# MCU_Schematic_Winterbreak.net
KiCad netlist of a schematic drawn in Altium Designer
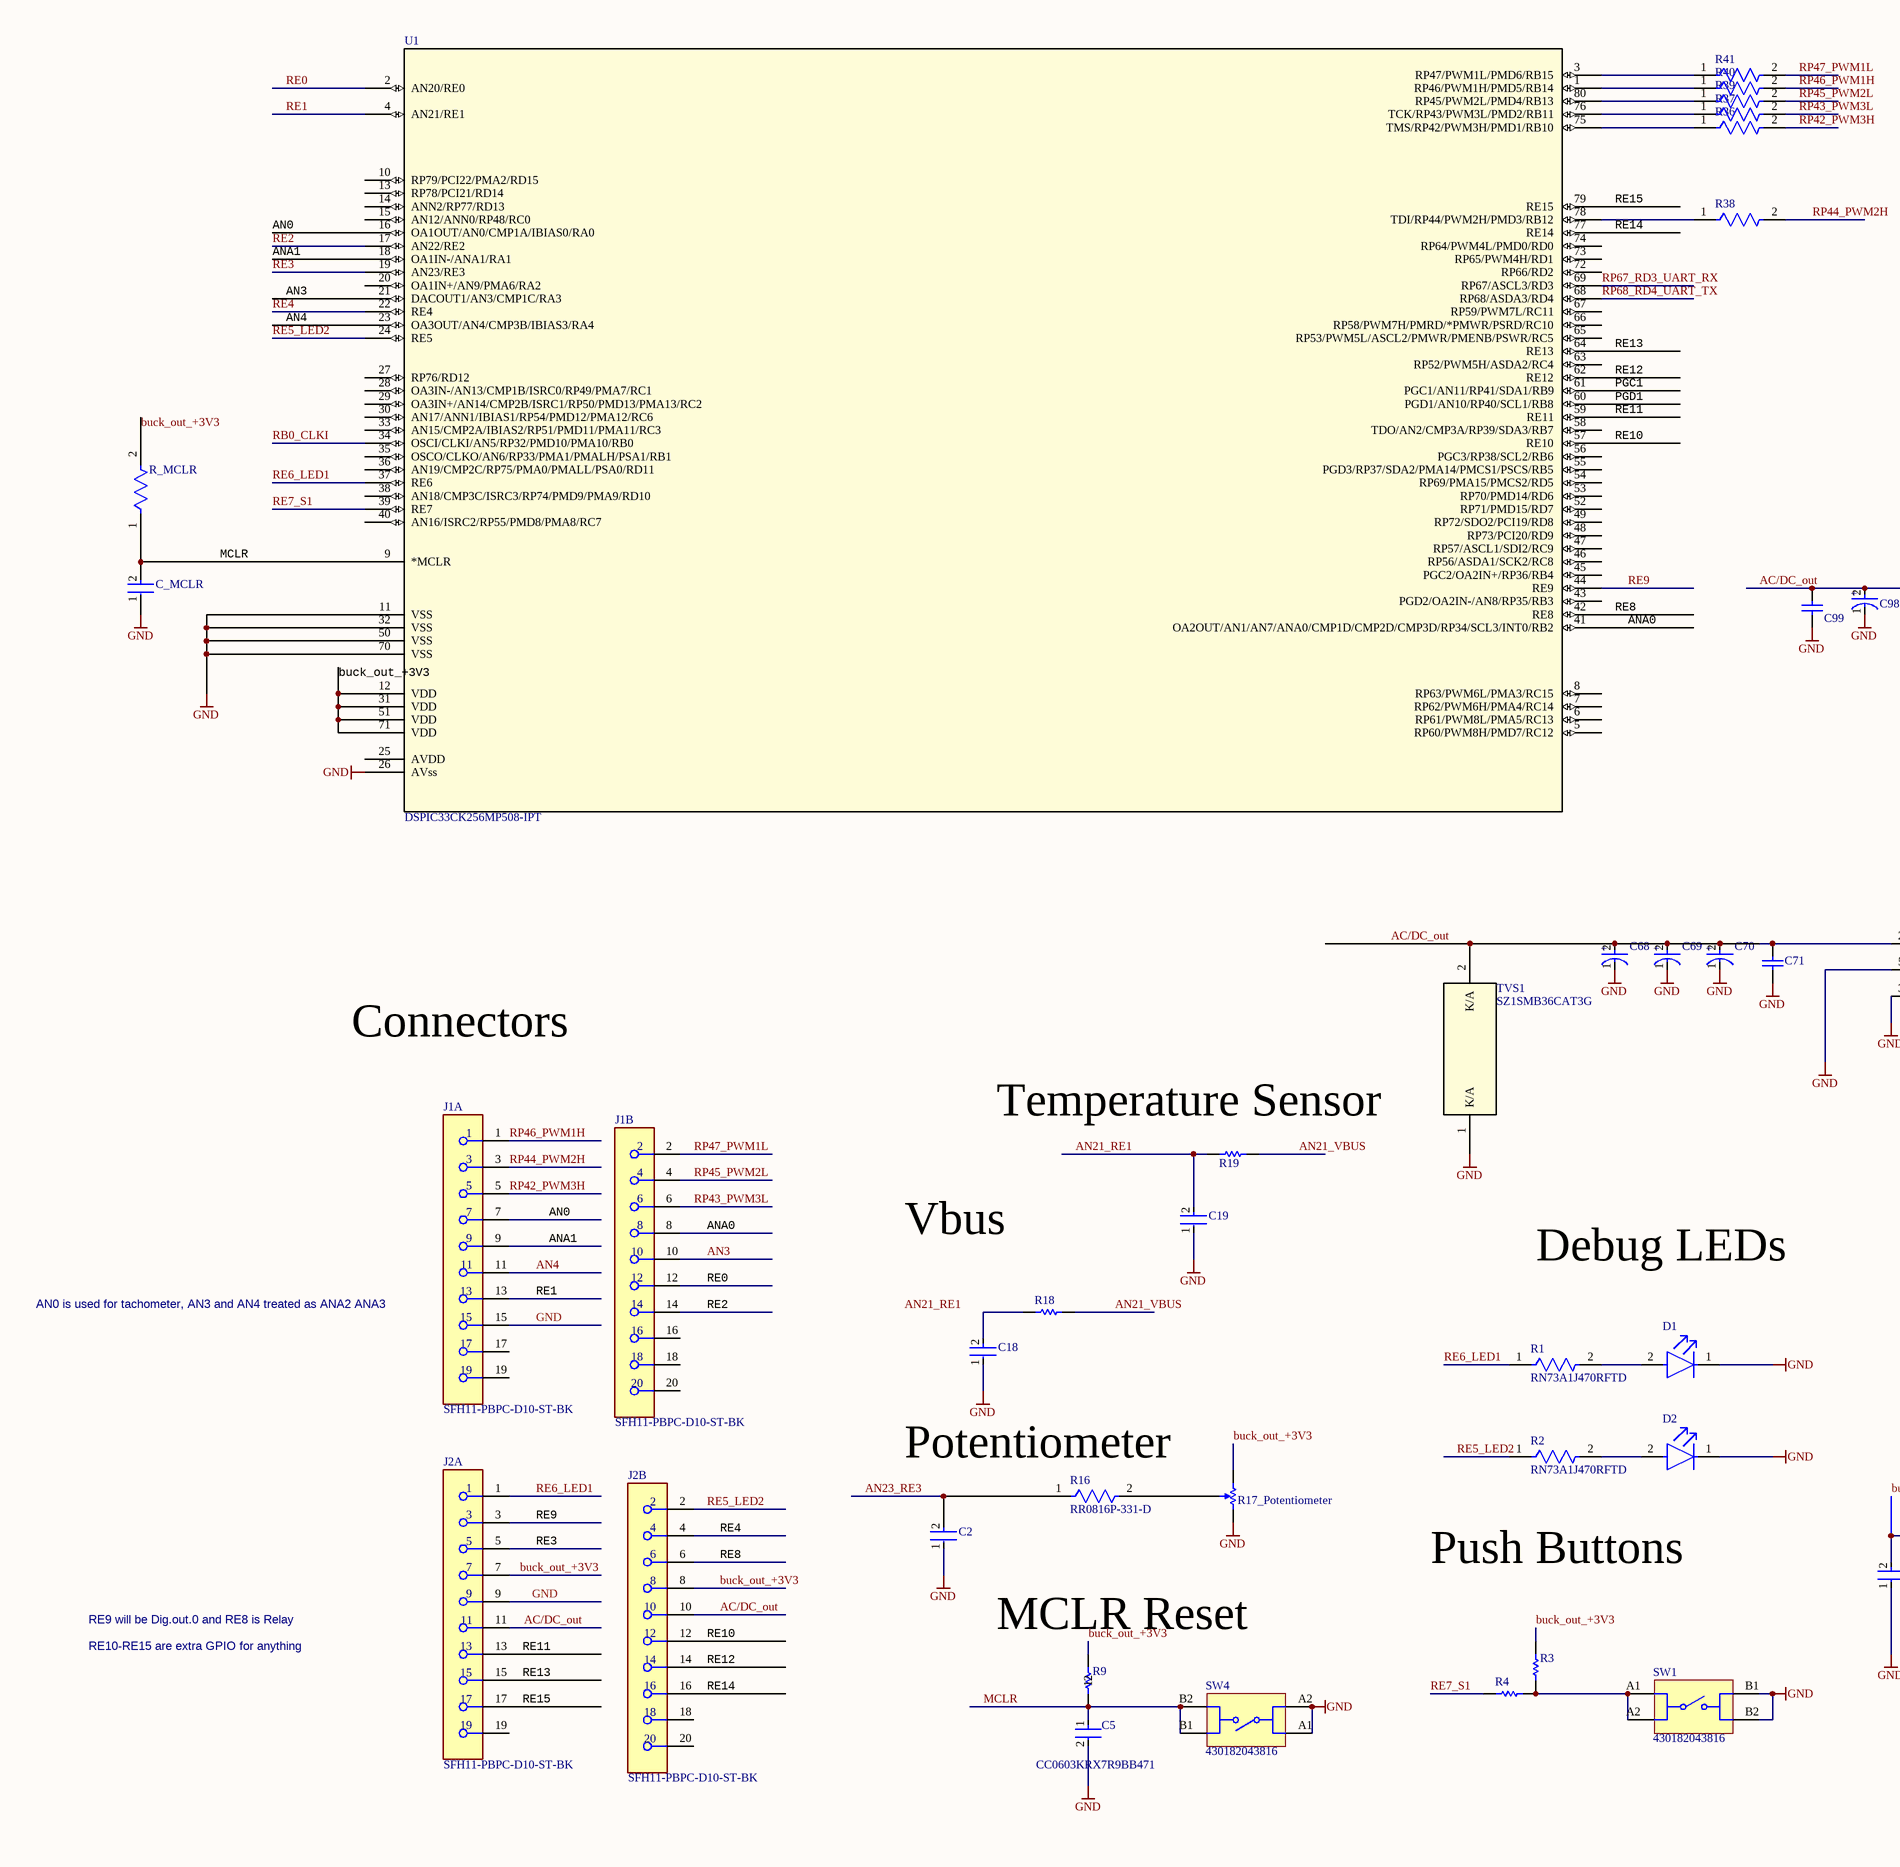
[diagram p0: MCU_Schematic_Winterbreak.SchDoc, left]
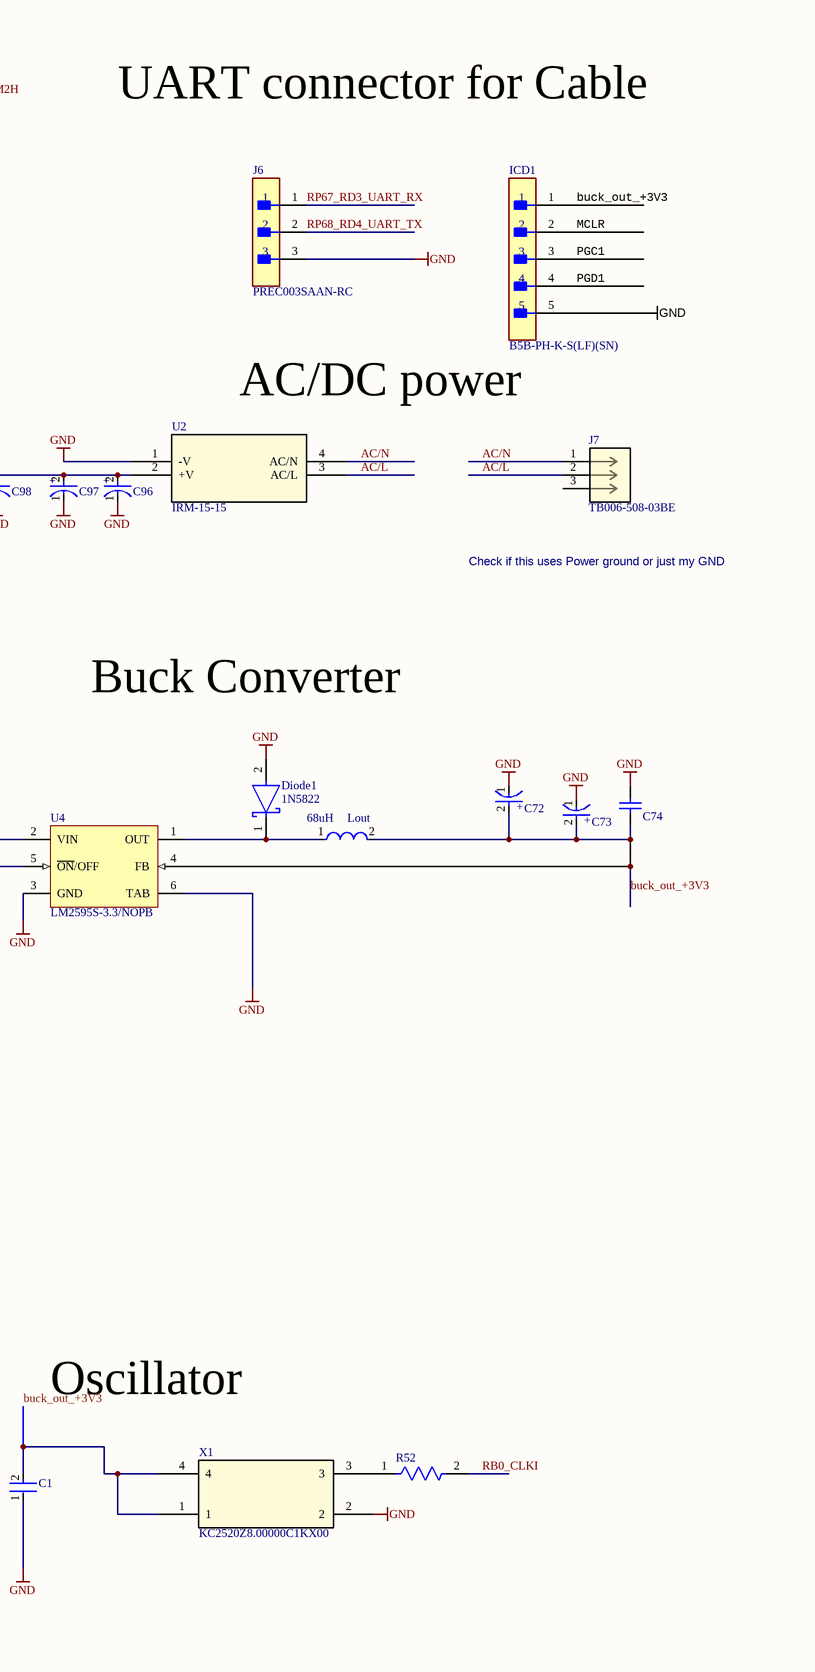
[diagram p1: MCU_Schematic_Winterbreak.SchDoc, right]

(export (version "E")
  (design (tool "Eeschema 10.0.6"))
  (components
    (comp (ref "C1")
      (value "GRM155R71C104KA88D")
      (footprint "FP-GRM15-MFG")
      (description "CAP CER 0.1UF 16V X7R 0402")
      (fields
        (field (name "TOLERANCE") "10%")
        (field (name "OCTOPART") "https://octopart.com/grm155r71c104ka88d-murata-196880")
      )
      (libsource (lib "Altium Content Vault") (part "236180d848d6139a670b325ea6854c9"))
    )
    (comp (ref "C2")
      (value "GRM155R71C104KA88D")
      (footprint "FP-GRM15-MFG")
      (description "CAP CER 0.1UF 16V X7R 0402")
      (fields
        (field (name "TOLERANCE") "10%")
        (field (name "OCTOPART") "https://octopart.com/grm155r71c104ka88d-murata-196880")
      )
      (libsource (lib "Altium Content Vault") (part "236180d848d6139a670b325ea6854c9"))
    )
    (comp (ref "C5")
      (value "CC0603KRX7R9BB471")
      (footprint "FP-CC0603-DA-MFG")
      (description "CAP CER 470PF 50V X7R 0603")
      (fields
        (field (name "VOLTAGE") "50 V")
        (field (name "OCTOPART") "https://octopart.com/cc0603krx7r9bb471-yageo-192931")
      )
      (libsource (lib "Altium Content Vault") (part "11868f565c42a9108669ba33697ecf6"))
    )
    (comp (ref "C18")
      (value "GRM155R71C104KA88D")
      (footprint "FP-GRM15-MFG")
      (description "CAP CER 0.1UF 16V X7R 0402")
      (fields
        (field (name "TOLERANCE") "10%")
        (field (name "OCTOPART") "https://octopart.com/grm155r71c104ka88d-murata-196880")
      )
      (libsource (lib "Altium Content Vault") (part "236180d848d6139a670b325ea6854c9"))
    )
    (comp (ref "C19")
      (value "GRM155R71C104KA88D")
      (footprint "FP-GRM15-MFG")
      (description "CAP CER 0.1UF 16V X7R 0402")
      (fields
        (field (name "TOLERANCE") "10%")
        (field (name "OCTOPART") "https://octopart.com/grm155r71c104ka88d-murata-196880")
      )
      (libsource (lib "Altium Content Vault") (part "236180d848d6139a670b325ea6854c9"))
    )
    (comp (ref "C68")
      (value "EEHAZS1H221B")
      (footprint "FP-EEHA-G16-MFG")
      (description "Conductive Polymer Hybrid Aluminum Electrolytic Capacitors 220uF ±20% 50V RADIAL TH 10x15.7mm")
      (libsource (lib "Altium Content Vault") (part "203bc49f2ac43e59fd269a8c329ed05"))
    )
    (comp (ref "C69")
      (value "EEHAZS1H221B")
      (footprint "FP-EEHA-G16-MFG")
      (description "Conductive Polymer Hybrid Aluminum Electrolytic Capacitors 220uF ±20% 50V RADIAL TH 10x15.7mm")
      (libsource (lib "Altium Content Vault") (part "203bc49f2ac43e59fd269a8c329ed05"))
    )
    (comp (ref "C70")
      (value "TAJE476K035RNJ")
      (footprint "FP-TAJE-MFG")
      (description "47uF 35V  ±10% 900mΩ 2917  SMD Tantalum Capacitor")
      (fields (field (name "VOLTAGE") "35V") (field (name "TOLERANCE") "10%"))
      (libsource (lib "Altium Content Vault") (part "203bc49f2ac43e59fd269a8c329ed05"))
    )
    (comp (ref "C71")
      (value "08055C104KAZ2A")
      (footprint "CAPC2013X94X50NL20T25")
      (fields (field (name "MANUFACTURER") "AVX Interconnect / Elco"))
      (libsource (lib "Altium Content Vault") (part "CAP"))
    )
    (comp (ref "C72")
      (value "EEHAZS1H221B")
      (footprint "FP-EEHA-G16-MFG")
      (description "Conductive Polymer Hybrid Aluminum Electrolytic Capacitors 220uF ±20% 50V RADIAL TH 10x15.7mm")
      (libsource (lib "Altium Content Vault") (part "203bc49f2ac43e59fd269a8c329ed05"))
    )
    (comp (ref "C73")
      (value "TAJE476K035RNJ")
      (footprint "FP-TAJE-MFG")
      (description "47uF 35V  ±10% 900mΩ 2917  SMD Tantalum Capacitor")
      (fields (field (name "VOLTAGE") "35V") (field (name "TOLERANCE") "10%"))
      (libsource (lib "Altium Content Vault") (part "203bc49f2ac43e59fd269a8c329ed05"))
    )
    (comp (ref "C74")
      (value "08055C104KAZ2A")
      (footprint "CAPC2013X94X50NL20T25")
      (fields (field (name "MANUFACTURER") "AVX Interconnect / Elco"))
      (libsource (lib "Altium Content Vault") (part "CAP"))
    )
    (comp (ref "C96")
      (value "EEHAZS1H221B")
      (footprint "FP-EEHA-G16-MFG")
      (description "Conductive Polymer Hybrid Aluminum Electrolytic Capacitors 220uF ±20% 50V RADIAL TH 10x15.7mm")
      (libsource (lib "Altium Content Vault") (part "203bc49f2ac43e59fd269a8c329ed05"))
    )
    (comp (ref "C97")
      (value "EEHAZS1H221B")
      (footprint "FP-EEHA-G16-MFG")
      (description "Conductive Polymer Hybrid Aluminum Electrolytic Capacitors 220uF ±20% 50V RADIAL TH 10x15.7mm")
      (libsource (lib "Altium Content Vault") (part "203bc49f2ac43e59fd269a8c329ed05"))
    )
    (comp (ref "C98")
      (value "TAJE476K035RNJ")
      (footprint "FP-TAJE-MFG")
      (description "47uF 35V  ±10% 900mΩ 2917  SMD Tantalum Capacitor")
      (fields (field (name "VOLTAGE") "35V") (field (name "TOLERANCE") "10%"))
      (libsource (lib "Altium Content Vault") (part "203bc49f2ac43e59fd269a8c329ed05"))
    )
    (comp (ref "C99")
      (value "08055C104KAZ2A")
      (footprint "CAPC2013X94X50NL20T25")
      (fields (field (name "MANUFACTURER") "AVX Interconnect / Elco"))
      (libsource (lib "Altium Content Vault") (part "CAP"))
    )
    (comp (ref "C_MCLR")
      (value "GRM155R71C104KA88D")
      (footprint "FP-GRM15-MFG")
      (description "CAP CER 0.1UF 16V X7R 0402")
      (fields
        (field (name "TOLERANCE") "10%")
        (field (name "OCTOPART") "https://octopart.com/grm155r71c104ka88d-murata-196880")
      )
      (libsource (lib "Altium Content Vault") (part "236180d848d6139a670b325ea6854c9"))
    )
    (comp (ref "D1")
      (value "LTST-C190KGKT")
      (footprint "FP-LTST-C190KGKT-MFG")
      (description "LED GREEN CLEAR CHIP SMD")
      (libsource (lib "Altium Content Vault") (part "8706943c75ba83719d021d2fdc84c58"))
    )
    (comp (ref "D2")
      (value "LTST-C190KGKT")
      (footprint "FP-LTST-C190KGKT-MFG")
      (description "LED GREEN CLEAR CHIP SMD")
      (libsource (lib "Altium Content Vault") (part "8706943c75ba83719d021d2fdc84c58"))
    )
    (comp (ref "Diode1")
      (value "1N5822")
      (footprint "FP-DO-201AD-MFG")
      (description "DIODE SCHOTTKY 40V 3A DO201AD")
      (fields
        (field (name "OCTOPART") "https://octopart.com/1n5822-stmicroelectronics-323225")
        (field (name "MANUFACTURER") "STMicroelectronics")
      )
      (libsource (lib "Altium Content Vault") (part "1d6ec82d83fb6aee721767c19dac4b9"))
    )
    (comp (ref "ICD1")
      (value "B5B-PH-K-S(LF)(SN)")
      (footprint "FP-B5B-PH-K-S_LF_SN-MFG")
      (description "CONN HEADER VERT 5POS 2MM")
      (libsource (lib "Altium Content Vault") (part "bf93c07fd2649a848d0ec8585582aab"))
    )
    (comp (ref "J1")
      (value "SFH11-PBPC-D10-ST-BK")
      (footprint "FP-SFH11-PBPC-D10-ST-BK-MFG")
      (description "CONN HDR 20POS 0.1 GOLD PCB")
      (libsource (lib "Altium Content Vault") (part "86e307fb827e6da12e54f1dde2f44ab"))
    )
    (comp (ref "J2")
      (value "SFH11-PBPC-D10-ST-BK")
      (footprint "FP-SFH11-PBPC-D10-ST-BK-MFG")
      (description "CONN HDR 20POS 0.1 GOLD PCB")
      (libsource (lib "Altium Content Vault") (part "86e307fb827e6da12e54f1dde2f44ab"))
    )
    (comp (ref "J6")
      (value "PREC003SAAN-RC")
      (footprint "FP-PREC003SAAN-RC-MFG")
      (description "PREC003SAAN-RC Conn Header Vert 3POS 2.54MM")
      (libsource (lib "Altium Content Vault") (part "0d3f023dd272f625e17a2be33dea85f"))
    )
    (comp (ref "J7")
      (value "TB006-508-03BE")
      (footprint "CONN3_TB006-508_CUD")
      (description "No Description Available")
      (libsource (lib "TB006-508-03BE") (part "TB006-508-03BE"))
    )
    (comp (ref "Lout")
      (value "NR6028T680M")
      (footprint "FP-NR6028-MFG")
      (description "SMD Power Inductors 68uH ±20% 0.76A 0.546Ω")
      (fields (field (name "TOLERANCE") "20%") (field (name "INDUCTANCE") "68uH"))
      (libsource (lib "Altium Content Vault") (part "725321dda6339637d4d059423bc1c3c"))
    )
    (comp (ref "R1")
      (value "RN73A1J470RFTD")
      (footprint "FP-RN731J-MFG")
      (description "42")
      (fields
        (field (name "MANUFACTURER") "TE Connectivity")
        (field (name "OCTOPART") "https://octopart.com/rn73a1j470rftd-te+connectivity-22740827")
      )
      (libsource (lib "Altium Content Vault") (part "1029c3af85768c4190bb7ad29bc67b5"))
    )
    (comp (ref "R2")
      (value "RN73A1J470RFTD")
      (footprint "FP-RN731J-MFG")
      (description "42")
      (fields
        (field (name "MANUFACTURER") "TE Connectivity")
        (field (name "OCTOPART") "https://octopart.com/rn73a1j470rftd-te+connectivity-22740827")
      )
      (libsource (lib "Altium Content Vault") (part "1029c3af85768c4190bb7ad29bc67b5"))
    )
    (comp (ref "R3")
      (value "ERJ3EKF1002V")
      (footprint "RESC1609X55X30LL15T15")
      (description "Chip Resistor, 10 KOhm, +/- 1%, 0.1 W, -55 to 155 degC, 0603 (1608 Metric), RoHS, Tape and Reel")
      (fields (field (name "TOLERANCE") "1%") (field (name "MANUFACTURER") "Panasonic"))
      (libsource (lib "Altium Content Vault") (part "RES-2"))
    )
    (comp (ref "R4")
      (value "ERJ-3EKF1001V")
      (footprint "RESC1608X55X30LL15T15")
      (fields (field (name "MANUFACTURER") "Panasonic"))
      (libsource (lib "Altium Content Vault") (part "RES"))
    )
    (comp (ref "R9")
      (value "ERJ3EKF1002V")
      (footprint "RESC1609X55X30LL15T15")
      (description "Chip Resistor, 10 KOhm, +/- 1%, 0.1 W, -55 to 155 degC, 0603 (1608 Metric), RoHS, Tape and Reel")
      (fields (field (name "TOLERANCE") "1%") (field (name "MANUFACTURER") "Panasonic"))
      (libsource (lib "") (part "RES-2_1"))
    )
    (comp (ref "R16")
      (value "RR0816P-331-D")
      (footprint "FP-RR0816-IPC_C")
      (description "330Ω ±0.5% 0.0625W 1/16W Chip Resistor 0603 (1608 Metric) Thin Film")
      (fields (field (name "TOLERANCE") "0.5%"))
      (libsource (lib "Altium Content Vault") (part "1029c3af85768c4190bb7ad29bc67b5"))
    )
    (comp (ref "R17_Potentiometer")
      (value "P090S-14T20BR10K")
      (footprint "RES-POT-3")
      (fields (field (name "TOLERANCE") "±20%") (field (name "MANUFACTURER") "BI Technologies"))
      (libsource (lib "Altium Content Vault") (part "RES-ADJ-3_A"))
    )
    (comp (ref "R18")
      (value "ERJ-3EKF1000V")
      (footprint "RESC1608X55X30LL15T15")
      (fields (field (name "MANUFACTURER") "Panasonic"))
      (libsource (lib "Altium Content Vault") (part "RES"))
    )
    (comp (ref "R19")
      (value "ERJ3EKF1002V")
      (footprint "RESC1609X55X30LL15T15")
      (description "Chip Resistor, 10 KOhm, +/- 1%, 0.1 W, -55 to 155 degC, 0603 (1608 Metric), RoHS, Tape and Reel")
      (fields (field (name "TOLERANCE") "1%") (field (name "MANUFACTURER") "Panasonic"))
      (libsource (lib "Altium Content Vault") (part "RES-2"))
    )
    (comp (ref "R36")
      (value "RR0816Q-750-D")
      (footprint "FP-RR0816-IPC_B")
      (description "75Ω ±0.5% 0.0625W 1/16W Chip Resistor 0603 (1608 Metric) Thin Film")
      (fields (field (name "TOLERANCE") "0.5%"))
      (libsource (lib "Altium Content Vault") (part "1029c3af85768c4190bb7ad29bc67b5"))
    )
    (comp (ref "R37")
      (value "RR0816Q-750-D")
      (footprint "FP-RR0816-IPC_B")
      (description "75Ω ±0.5% 0.0625W 1/16W Chip Resistor 0603 (1608 Metric) Thin Film")
      (fields (field (name "TOLERANCE") "0.5%"))
      (libsource (lib "Altium Content Vault") (part "1029c3af85768c4190bb7ad29bc67b5"))
    )
    (comp (ref "R38")
      (value "RR0816Q-750-D")
      (footprint "FP-RR0816-IPC_B")
      (description "75Ω ±0.5% 0.0625W 1/16W Chip Resistor 0603 (1608 Metric) Thin Film")
      (fields (field (name "TOLERANCE") "0.5%"))
      (libsource (lib "Altium Content Vault") (part "1029c3af85768c4190bb7ad29bc67b5"))
    )
    (comp (ref "R39")
      (value "RR0816Q-750-D")
      (footprint "FP-RR0816-IPC_B")
      (description "75Ω ±0.5% 0.0625W 1/16W Chip Resistor 0603 (1608 Metric) Thin Film")
      (fields (field (name "TOLERANCE") "0.5%"))
      (libsource (lib "Altium Content Vault") (part "1029c3af85768c4190bb7ad29bc67b5"))
    )
    (comp (ref "R40")
      (value "RR0816Q-750-D")
      (footprint "FP-RR0816-IPC_B")
      (description "75Ω ±0.5% 0.0625W 1/16W Chip Resistor 0603 (1608 Metric) Thin Film")
      (fields (field (name "TOLERANCE") "0.5%"))
      (libsource (lib "Altium Content Vault") (part "1029c3af85768c4190bb7ad29bc67b5"))
    )
    (comp (ref "R41")
      (value "RR0816Q-750-D")
      (footprint "FP-RR0816-IPC_B")
      (description "75Ω ±0.5% 0.0625W 1/16W Chip Resistor 0603 (1608 Metric) Thin Film")
      (fields (field (name "TOLERANCE") "0.5%"))
      (libsource (lib "Altium Content Vault") (part "1029c3af85768c4190bb7ad29bc67b5"))
    )
    (comp (ref "R52")
      (value "RR0816Q-750-D")
      (footprint "FP-RR0816-IPC_B")
      (description "75Ω ±0.5% 0.0625W 1/16W Chip Resistor 0603 (1608 Metric) Thin Film")
      (fields (field (name "TOLERANCE") "0.5%"))
      (libsource (lib "Altium Content Vault") (part "1029c3af85768c4190bb7ad29bc67b5"))
    )
    (comp (ref "R_MCLR")
      (value "ESR03EZPJ103")
      (footprint "FP-ESR03-IPC_C")
      (description "10kΩ ±5% 0.25W 0603 Anti-Surge Chip Resistor AEC-Q200")
      (fields (field (name "TOLERANCE") "5%"))
      (libsource (lib "Altium Content Vault") (part "1029c3af85768c4190bb7ad29bc67b5"))
    )
    (comp (ref "SW1")
      (value "430182043816")
      (footprint "430182043816")
      (description "Switch Tactile N.O. SPST Round Button Gull Wing 0.05A 12VDC 1000000Cycles 1.57N SMD Reel")
      (libsource (lib "Altium Content Vault") (part "SPST-NO_4P"))
    )
    (comp (ref "SW4")
      (value "430182043816")
      (footprint "430182043816")
      (description "Switch Tactile N.O. SPST Round Button Gull Wing 0.05A 12VDC 1000000Cycles 1.57N SMD Reel")
      (libsource (lib "") (part "SPST-NO_4P_1"))
    )
    (comp (ref "TVS1")
      (value "SZ1SMB36CAT3G")
      (footprint "SMB-2_4P60X3P95_ONS")
      (description "No Description Available")
      (libsource (lib "SZ1SMB36CAT3G") (part "SZ1SMB36CAT3G"))
    )
    (comp (ref "U1")
      (value "DSPIC33CK256MP508-IPT")
      (footprint "TQFP80_PT_MCH")
      (description "No Description Available")
      (libsource (lib "DSPIC33CK256MP508-IPT") (part "DSPIC33CK256MP508-IPT"))
    )
    (comp (ref "U2")
      (value "IRM-15-15")
      (footprint "IRM-15_MWU")
      (description "No Description Available")
      (libsource (lib "IRM-15-15") (part "IRM-15-15"))
    )
    (comp (ref "U4")
      (value "LM2595S-3.3/NOPB")
      (footprint "KTT0005B_N")
      (description "SIMPLE SWITCHER® Power Converter 150 KHz 1A Step-Down Voltage Regulator, 5-pin TO-263, Pb-Free")
      (fields (field (name "MANUFACTURER") "Texas Instruments"))
      (libsource (lib "Altium Content Vault") (part "PM-REG-LM2595S-12"))
    )
    (comp (ref "X1")
      (value "KC2520Z8.00000C1KX00")
      (footprint "OSC_0C1KX00_AVX")
      (description "No Description Available")
      (libsource (lib "KC2520Z8P00000C1KX00") (part "KC2520Z8.00000C1KX00"))
    )
  )
  (nets
    (net (code "1") (name "/AC{slash}DC_out") (class "Default")
      (node (ref "C68") (pin "2") (pinfunction "A_2") (pintype "passive"))
      (node (ref "C69") (pin "2") (pinfunction "A_2") (pintype "passive"))
      (node (ref "C70") (pin "2") (pinfunction "A_2") (pintype "passive"))
      (node (ref "C71") (pin "2") (pinfunction "2_2") (pintype "passive"))
      (node (ref "C96") (pin "2") (pinfunction "A_2") (pintype "passive"))
      (node (ref "C97") (pin "2") (pinfunction "A_2") (pintype "passive"))
      (node (ref "C98") (pin "2") (pinfunction "A_2") (pintype "passive"))
      (node (ref "C99") (pin "2") (pinfunction "2_2") (pintype "passive"))
      (node (ref "J2") (pin "10") (pinfunction "10_10") (pintype "passive"))
      (node (ref "J2") (pin "11") (pinfunction "11_11") (pintype "passive"))
      (node (ref "TVS1") (pin "2") (pinfunction "K/A_2") (pintype "passive"))
      (node (ref "U2") (pin "2") (pinfunction "+V_2") (pintype "power_in"))
      (node (ref "U4") (pin "2") (pinfunction "VIN_2") (pintype "power_in"))
    )
    (net (code "2") (name "/AC{slash}L") (class "Default")
      (node (ref "J7") (pin "2") (pinfunction "2_2") (pintype "passive"))
      (node (ref "U2") (pin "3") (pinfunction "AC/L_3") (pintype "passive"))
    )
    (net (code "3") (name "/AC{slash}N") (class "Default")
      (node (ref "J7") (pin "1") (pinfunction "1_1") (pintype "passive"))
      (node (ref "U2") (pin "4") (pinfunction "AC/N_4") (pintype "passive"))
    )
    (net (code "4") (name "/AN0") (class "Default")
      (node (ref "J1") (pin "7") (pinfunction "7_7") (pintype "passive"))
      (node (ref "U1") (pin "16") (pinfunction "OA1OUT/AN0/CMP1A/IBIAS0/RA0_16") (pintype "bidirectional"))
    )
    (net (code "5") (name "/AN3") (class "Default")
      (node (ref "J1") (pin "10") (pinfunction "10_10") (pintype "passive"))
      (node (ref "U1") (pin "21") (pinfunction "DACOUT1/AN3/CMP1C/RA3_21") (pintype "bidirectional"))
    )
    (net (code "6") (name "/AN4") (class "Default")
      (node (ref "J1") (pin "11") (pinfunction "11_11") (pintype "passive"))
      (node (ref "U1") (pin "23") (pinfunction "OA3OUT/AN4/CMP3B/IBIAS3/RA4_23") (pintype "bidirectional"))
    )
    (net (code "7") (name "/AN21_RE1") (class "Default")
      (node (ref "C19") (pin "2") (pinfunction "2_2") (pintype "passive"))
      (node (ref "R19") (pin "2") (pinfunction "2_2") (pintype "passive"))
    )
    (net (code "8") (name "/AN21_VBUS") (class "Default")
      (node (ref "R18") (pin "2") (pinfunction "2_2") (pintype "passive"))
      (node (ref "R19") (pin "1") (pinfunction "1_1") (pintype "passive"))
    )
    (net (code "9") (name "/AN23_RE3") (class "Default")
      (node (ref "C2") (pin "2") (pinfunction "2_2") (pintype "passive"))
      (node (ref "R16") (pin "1") (pinfunction "1_1") (pintype "passive"))
    )
    (net (code "10") (name "/ANA0") (class "Default")
      (node (ref "J1") (pin "8") (pinfunction "8_8") (pintype "passive"))
      (node (ref "U1") (pin "41") (pinfunction "OA2OUT/AN1/AN7/ANA0/CMP1D/CMP2D/CMP3D/RP34/SCL3/INT0/RB2_41") (pintype "bidirectional"))
    )
    (net (code "11") (name "/ANA1") (class "Default")
      (node (ref "J1") (pin "9") (pinfunction "9_9") (pintype "passive"))
      (node (ref "U1") (pin "18") (pinfunction "OA1IN-/ANA1/RA1_18") (pintype "bidirectional"))
    )
    (net (code "12") (name "/MCLR") (class "Default")
      (node (ref "C5") (pin "1") (pinfunction "1_1") (pintype "passive"))
      (node (ref "C_MCLR") (pin "2") (pinfunction "2_2") (pintype "passive"))
      (node (ref "ICD1") (pin "2") (pinfunction "2_2") (pintype "passive"))
      (node (ref "R9") (pin "1") (pinfunction "1_1") (pintype "passive"))
      (node (ref "R_MCLR") (pin "1") (pinfunction "1_1") (pintype "passive"))
      (node (ref "SW4") (pin "B1") (pinfunction "B1_B1") (pintype "passive"))
      (node (ref "SW4") (pin "B2") (pinfunction "B2_B2") (pintype "passive"))
      (node (ref "U1") (pin "9") (pinfunction "*MCLR_9") (pintype "passive"))
    )
    (net (code "13") (name "/PGC1") (class "Default")
      (node (ref "ICD1") (pin "3") (pinfunction "3_3") (pintype "passive"))
      (node (ref "U1") (pin "61") (pinfunction "PGC1/AN11/RP41/SDA1/RB9_61") (pintype "bidirectional"))
    )
    (net (code "14") (name "/PGD1") (class "Default")
      (node (ref "ICD1") (pin "4") (pinfunction "4_4") (pintype "passive"))
      (node (ref "U1") (pin "60") (pinfunction "PGD1/AN10/RP40/SCL1/RB8_60") (pintype "bidirectional"))
    )
    (net (code "15") (name "/RB0_CLKI") (class "Default")
      (node (ref "R52") (pin "2") (pinfunction "2_2") (pintype "passive"))
      (node (ref "U1") (pin "34") (pinfunction "OSCI/CLKI/AN5/RP32/PMD10/PMA10/RB0_34") (pintype "bidirectional"))
    )
    (net (code "16") (name "/RE0") (class "Default")
      (node (ref "J1") (pin "12") (pinfunction "12_12") (pintype "passive"))
      (node (ref "U1") (pin "2") (pinfunction "AN20/RE0_2") (pintype "bidirectional"))
    )
    (net (code "17") (name "/RE1") (class "Default")
      (node (ref "J1") (pin "13") (pinfunction "13_13") (pintype "passive"))
      (node (ref "U1") (pin "4") (pinfunction "AN21/RE1_4") (pintype "bidirectional"))
    )
    (net (code "18") (name "/RE2") (class "Default")
      (node (ref "J1") (pin "14") (pinfunction "14_14") (pintype "passive"))
      (node (ref "U1") (pin "17") (pinfunction "AN22/RE2_17") (pintype "bidirectional"))
    )
    (net (code "19") (name "/RE3") (class "Default")
      (node (ref "J2") (pin "5") (pinfunction "5_5") (pintype "passive"))
      (node (ref "U1") (pin "19") (pinfunction "AN23/RE3_19") (pintype "bidirectional"))
    )
    (net (code "20") (name "/RE4") (class "Default")
      (node (ref "J2") (pin "4") (pinfunction "4_4") (pintype "passive"))
      (node (ref "U1") (pin "22") (pinfunction "RE4_22") (pintype "bidirectional"))
    )
    (net (code "21") (name "/RE5_LED2") (class "Default")
      (node (ref "J2") (pin "2") (pinfunction "2_2") (pintype "passive"))
      (node (ref "R2") (pin "1") (pinfunction "1_1") (pintype "passive"))
      (node (ref "U1") (pin "24") (pinfunction "RE5_24") (pintype "bidirectional"))
    )
    (net (code "22") (name "/RE6_LED1") (class "Default")
      (node (ref "J2") (pin "1") (pinfunction "1_1") (pintype "passive"))
      (node (ref "R1") (pin "1") (pinfunction "1_1") (pintype "passive"))
      (node (ref "U1") (pin "37") (pinfunction "RE6_37") (pintype "bidirectional"))
    )
    (net (code "23") (name "/RE7_S1") (class "Default")
      (node (ref "R4") (pin "1") (pinfunction "1_1") (pintype "passive"))
      (node (ref "U1") (pin "39") (pinfunction "RE7_39") (pintype "bidirectional"))
    )
    (net (code "24") (name "/RE8") (class "Default")
      (node (ref "J2") (pin "6") (pinfunction "6_6") (pintype "passive"))
      (node (ref "U1") (pin "42") (pinfunction "RE8_42") (pintype "bidirectional"))
    )
    (net (code "25") (name "/RE9") (class "Default")
      (node (ref "J2") (pin "3") (pinfunction "3_3") (pintype "passive"))
      (node (ref "U1") (pin "44") (pinfunction "RE9_44") (pintype "bidirectional"))
    )
    (net (code "26") (name "/RE10") (class "Default")
      (node (ref "J2") (pin "12") (pinfunction "12_12") (pintype "passive"))
      (node (ref "U1") (pin "57") (pinfunction "RE10_57") (pintype "bidirectional"))
    )
    (net (code "27") (name "/RE11") (class "Default")
      (node (ref "J2") (pin "13") (pinfunction "13_13") (pintype "passive"))
      (node (ref "U1") (pin "59") (pinfunction "RE11_59") (pintype "bidirectional"))
    )
    (net (code "28") (name "/RE12") (class "Default")
      (node (ref "J2") (pin "14") (pinfunction "14_14") (pintype "passive"))
      (node (ref "U1") (pin "62") (pinfunction "RE12_62") (pintype "bidirectional"))
    )
    (net (code "29") (name "/RE13") (class "Default")
      (node (ref "J2") (pin "15") (pinfunction "15_15") (pintype "passive"))
      (node (ref "U1") (pin "64") (pinfunction "RE13_64") (pintype "bidirectional"))
    )
    (net (code "30") (name "/RE14") (class "Default")
      (node (ref "J2") (pin "16") (pinfunction "16_16") (pintype "passive"))
      (node (ref "U1") (pin "77") (pinfunction "RE14_77") (pintype "bidirectional"))
    )
    (net (code "31") (name "/RE15") (class "Default")
      (node (ref "J2") (pin "17") (pinfunction "17_17") (pintype "passive"))
      (node (ref "U1") (pin "79") (pinfunction "RE15_79") (pintype "bidirectional"))
    )
    (net (code "32") (name "/RP42_PWM3H") (class "Default")
      (node (ref "J1") (pin "5") (pinfunction "5_5") (pintype "passive"))
      (node (ref "R36") (pin "2") (pinfunction "2_2") (pintype "passive"))
    )
    (net (code "33") (name "/RP43_PWM3L") (class "Default")
      (node (ref "J1") (pin "6") (pinfunction "6_6") (pintype "passive"))
      (node (ref "R37") (pin "2") (pinfunction "2_2") (pintype "passive"))
    )
    (net (code "34") (name "/RP44_PWM2H") (class "Default")
      (node (ref "J1") (pin "3") (pinfunction "3_3") (pintype "passive"))
      (node (ref "R38") (pin "2") (pinfunction "2_2") (pintype "passive"))
    )
    (net (code "35") (name "/RP45_PWM2L") (class "Default")
      (node (ref "J1") (pin "4") (pinfunction "4_4") (pintype "passive"))
      (node (ref "R39") (pin "2") (pinfunction "2_2") (pintype "passive"))
    )
    (net (code "36") (name "/RP46_PWM1H") (class "Default")
      (node (ref "J1") (pin "1") (pinfunction "1_1") (pintype "passive"))
      (node (ref "R40") (pin "2") (pinfunction "2_2") (pintype "passive"))
    )
    (net (code "37") (name "/RP47_PWM1L") (class "Default")
      (node (ref "J1") (pin "2") (pinfunction "2_2") (pintype "passive"))
      (node (ref "R41") (pin "2") (pinfunction "2_2") (pintype "passive"))
    )
    (net (code "38") (name "/RP67_RD3_UART_RX") (class "Default")
      (node (ref "J6") (pin "1") (pinfunction "1_1") (pintype "passive"))
      (node (ref "U1") (pin "69") (pinfunction "RP67/ASCL3/RD3_69") (pintype "bidirectional"))
    )
    (net (code "39") (name "/RP68_RD4_UART_TX") (class "Default")
      (node (ref "J6") (pin "2") (pinfunction "2_2") (pintype "passive"))
      (node (ref "U1") (pin "68") (pinfunction "RP68/ASDA3/RD4_68") (pintype "bidirectional"))
    )
    (net (code "40") (name "/buck_out_+3V3") (class "Default")
      (node (ref "C1") (pin "2") (pinfunction "2_2") (pintype "passive"))
      (node (ref "C72") (pin "2") (pinfunction "A_2") (pintype "passive"))
      (node (ref "C73") (pin "2") (pinfunction "A_2") (pintype "passive"))
      (node (ref "C74") (pin "2") (pinfunction "2_2") (pintype "passive"))
      (node (ref "ICD1") (pin "1") (pinfunction "1_1") (pintype "passive"))
      (node (ref "J2") (pin "7") (pinfunction "7_7") (pintype "passive"))
      (node (ref "J2") (pin "8") (pinfunction "8_8") (pintype "passive"))
      (node (ref "Lout") (pin "2") (pinfunction "2_2") (pintype "passive"))
      (node (ref "R17_Potentiometer") (pin "1") (pinfunction "1_1") (pintype "passive"))
      (node (ref "R3") (pin "2") (pinfunction "2_2") (pintype "passive"))
      (node (ref "R9") (pin "2") (pinfunction "2_2") (pintype "passive"))
      (node (ref "R_MCLR") (pin "2") (pinfunction "2_2") (pintype "passive"))
      (node (ref "U1") (pin "12") (pinfunction "VDD_12") (pintype "power_in"))
      (node (ref "U1") (pin "31") (pinfunction "VDD_31") (pintype "power_in"))
      (node (ref "U1") (pin "51") (pinfunction "VDD_51") (pintype "power_in"))
      (node (ref "U1") (pin "71") (pinfunction "VDD_71") (pintype "power_in"))
      (node (ref "U4") (pin "4") (pinfunction "FB_4") (pintype "input"))
      (node (ref "X1") (pin "1") (pinfunction "1_1") (pintype "passive"))
      (node (ref "X1") (pin "4") (pinfunction "4_4") (pintype "passive"))
    )
    (net (code "41") (name "GND") (class "Default")
      (node (ref "C1") (pin "1") (pinfunction "1_1") (pintype "passive"))
      (node (ref "C18") (pin "1") (pinfunction "1_1") (pintype "passive"))
      (node (ref "C19") (pin "1") (pinfunction "1_1") (pintype "passive"))
      (node (ref "C2") (pin "1") (pinfunction "1_1") (pintype "passive"))
      (node (ref "C5") (pin "2") (pinfunction "2_2") (pintype "passive"))
      (node (ref "C68") (pin "1") (pinfunction "C_1") (pintype "passive"))
      (node (ref "C69") (pin "1") (pinfunction "C_1") (pintype "passive"))
      (node (ref "C70") (pin "1") (pinfunction "C_1") (pintype "passive"))
      (node (ref "C71") (pin "1") (pinfunction "1_1") (pintype "passive"))
      (node (ref "C72") (pin "1") (pinfunction "C_1") (pintype "passive"))
      (node (ref "C73") (pin "1") (pinfunction "C_1") (pintype "passive"))
      (node (ref "C74") (pin "1") (pinfunction "1_1") (pintype "passive"))
      (node (ref "C96") (pin "1") (pinfunction "C_1") (pintype "passive"))
      (node (ref "C97") (pin "1") (pinfunction "C_1") (pintype "passive"))
      (node (ref "C98") (pin "1") (pinfunction "C_1") (pintype "passive"))
      (node (ref "C99") (pin "1") (pinfunction "1_1") (pintype "passive"))
      (node (ref "C_MCLR") (pin "1") (pinfunction "1_1") (pintype "passive"))
      (node (ref "D1") (pin "1") (pinfunction "C_1") (pintype "passive"))
      (node (ref "D2") (pin "1") (pinfunction "C_1") (pintype "passive"))
      (node (ref "Diode1") (pin "2") (pinfunction "A_2") (pintype "passive"))
      (node (ref "ICD1") (pin "5") (pinfunction "5_5") (pintype "passive"))
      (node (ref "J1") (pin "15") (pinfunction "15_15") (pintype "passive"))
      (node (ref "J2") (pin "9") (pinfunction "9_9") (pintype "passive"))
      (node (ref "J6") (pin "3") (pinfunction "3_3") (pintype "passive"))
      (node (ref "R17_Potentiometer") (pin "3") (pinfunction "3_3") (pintype "passive"))
      (node (ref "SW1") (pin "B1") (pinfunction "B1_B1") (pintype "passive"))
      (node (ref "SW1") (pin "B2") (pinfunction "B2_B2") (pintype "passive"))
      (node (ref "SW4") (pin "A1") (pinfunction "A1_A1") (pintype "passive"))
      (node (ref "SW4") (pin "A2") (pinfunction "A2_A2") (pintype "passive"))
      (node (ref "TVS1") (pin "1") (pinfunction "K/A_1") (pintype "passive"))
      (node (ref "U1") (pin "11") (pinfunction "VSS_11") (pintype "power_in"))
      (node (ref "U1") (pin "26") (pinfunction "AVss_26") (pintype "power_in"))
      (node (ref "U1") (pin "32") (pinfunction "VSS_32") (pintype "power_in"))
      (node (ref "U1") (pin "50") (pinfunction "VSS_50") (pintype "power_in"))
      (node (ref "U1") (pin "70") (pinfunction "VSS_70") (pintype "power_in"))
      (node (ref "U2") (pin "1") (pinfunction "-V_1") (pintype "power_in"))
      (node (ref "U4") (pin "3") (pinfunction "GND_3") (pintype "power_in"))
      (node (ref "U4") (pin "5") (pinfunction "~{ON}/OFF_5") (pintype "input"))
      (node (ref "U4") (pin "6") (pinfunction "TAB_6") (pintype "power_in"))
      (node (ref "X1") (pin "2") (pinfunction "2_2") (pintype "passive"))
    )
    (net (code "42") (name "Net-(C18-Pad2)") (class "Default")
      (node (ref "C18") (pin "2") (pinfunction "2_2") (pintype "passive"))
      (node (ref "R18") (pin "1") (pinfunction "1_1") (pintype "passive"))
    )
    (net (code "43") (name "Net-(D1-A)") (class "Default")
      (node (ref "D1") (pin "2") (pinfunction "A_2") (pintype "passive"))
      (node (ref "R1") (pin "2") (pinfunction "2_2") (pintype "passive"))
    )
    (net (code "44") (name "Net-(D2-A)") (class "Default")
      (node (ref "D2") (pin "2") (pinfunction "A_2") (pintype "passive"))
      (node (ref "R2") (pin "2") (pinfunction "2_2") (pintype "passive"))
    )
    (net (code "45") (name "Net-(Diode1-C)") (class "Default")
      (node (ref "Diode1") (pin "1") (pinfunction "C_1") (pintype "passive"))
      (node (ref "Lout") (pin "1") (pinfunction "1_1") (pintype "passive"))
      (node (ref "U4") (pin "1") (pinfunction "OUT_1") (pintype "power_in"))
    )
    (net (code "46") (name "Net-(R3-Pad1)") (class "Default")
      (node (ref "R3") (pin "1") (pinfunction "1_1") (pintype "passive"))
      (node (ref "R4") (pin "2") (pinfunction "2_2") (pintype "passive"))
      (node (ref "SW1") (pin "A1") (pinfunction "A1_A1") (pintype "passive"))
      (node (ref "SW1") (pin "A2") (pinfunction "A2_A2") (pintype "passive"))
    )
    (net (code "47") (name "Net-(R16-Pad2)") (class "Default")
      (node (ref "R16") (pin "2") (pinfunction "2_2") (pintype "passive"))
      (node (ref "R17_Potentiometer") (pin "2") (pinfunction "2_2") (pintype "passive"))
    )
    (net (code "48") (name "Net-(R52-Pad1)") (class "Default")
      (node (ref "R52") (pin "1") (pinfunction "1_1") (pintype "passive"))
      (node (ref "X1") (pin "3") (pinfunction "3_3") (pintype "passive"))
    )
    (net (code "49") (name "Net-(U1-RP45{slash}PWM2L{slash}PMD4{slash}RB13)") (class "Default")
      (node (ref "R39") (pin "1") (pinfunction "1_1") (pintype "passive"))
      (node (ref "U1") (pin "80") (pinfunction "RP45/PWM2L/PMD4/RB13_80") (pintype "bidirectional"))
    )
    (net (code "50") (name "Net-(U1-RP46{slash}PWM1H{slash}PMD5{slash}RB14)") (class "Default")
      (node (ref "R40") (pin "1") (pinfunction "1_1") (pintype "passive"))
      (node (ref "U1") (pin "1") (pinfunction "RP46/PWM1H/PMD5/RB14_1") (pintype "bidirectional"))
    )
    (net (code "51") (name "Net-(U1-RP47{slash}PWM1L{slash}PMD6{slash}RB15)") (class "Default")
      (node (ref "R41") (pin "1") (pinfunction "1_1") (pintype "passive"))
      (node (ref "U1") (pin "3") (pinfunction "RP47/PWM1L/PMD6/RB15_3") (pintype "bidirectional"))
    )
    (net (code "52") (name "Net-(U1-TCK{slash}RP43{slash}PWM3L{slash}PMD2{slash}RB11)") (class "Default")
      (node (ref "R37") (pin "1") (pinfunction "1_1") (pintype "passive"))
      (node (ref "U1") (pin "76") (pinfunction "TCK/RP43/PWM3L/PMD2/RB11_76") (pintype "bidirectional"))
    )
    (net (code "53") (name "Net-(U1-TDI{slash}RP44{slash}PWM2H{slash}PMD3{slash}RB12)") (class "Default")
      (node (ref "R38") (pin "1") (pinfunction "1_1") (pintype "passive"))
      (node (ref "U1") (pin "78") (pinfunction "TDI/RP44/PWM2H/PMD3/RB12_78") (pintype "bidirectional"))
    )
    (net (code "54") (name "Net-(U1-TMS{slash}RP42{slash}PWM3H{slash}PMD1{slash}RB10)") (class "Default")
      (node (ref "R36") (pin "1") (pinfunction "1_1") (pintype "passive"))
      (node (ref "U1") (pin "75") (pinfunction "TMS/RP42/PWM3H/PMD1/RB10_75") (pintype "bidirectional"))
    )
    (net (code "55") (name "unconnected-(J1-Pad16)") (class "Default")
      (node (ref "J1") (pin "16") (pinfunction "16_16") (pintype "passive"))
    )
    (net (code "56") (name "unconnected-(J1-Pad17)") (class "Default")
      (node (ref "J1") (pin "17") (pinfunction "17_17") (pintype "passive"))
    )
    (net (code "57") (name "unconnected-(J1-Pad18)") (class "Default")
      (node (ref "J1") (pin "18") (pinfunction "18_18") (pintype "passive"))
    )
    (net (code "58") (name "unconnected-(J1-Pad19)") (class "Default")
      (node (ref "J1") (pin "19") (pinfunction "19_19") (pintype "passive"))
    )
    (net (code "59") (name "unconnected-(J1-Pad20)") (class "Default")
      (node (ref "J1") (pin "20") (pinfunction "20_20") (pintype "passive"))
    )
    (net (code "60") (name "unconnected-(J2-Pad18)") (class "Default")
      (node (ref "J2") (pin "18") (pinfunction "18_18") (pintype "passive"))
    )
    (net (code "61") (name "unconnected-(J2-Pad19)") (class "Default")
      (node (ref "J2") (pin "19") (pinfunction "19_19") (pintype "passive"))
    )
    (net (code "62") (name "unconnected-(J2-Pad20)") (class "Default")
      (node (ref "J2") (pin "20") (pinfunction "20_20") (pintype "passive"))
    )
    (net (code "63") (name "unconnected-(J7-Pad3)") (class "Default")
      (node (ref "J7") (pin "3") (pinfunction "3_3") (pintype "passive"))
    )
    (net (code "64") (name "unconnected-(U1-AN12{slash}ANN0{slash}RP48{slash}RC0-Pad15)") (class "Default")
      (node (ref "U1") (pin "15") (pinfunction "AN12/ANN0/RP48/RC0_15") (pintype "bidirectional"))
    )
    (net (code "65") (name "unconnected-(U1-AN15{slash}CMP2A{slash}IBIAS2{slash}RP51{slash}PMD11{slash}PMA11{slash}RC3-Pad33)") (class "Default")
      (node (ref "U1") (pin "33") (pinfunction "AN15/CMP2A/IBIAS2/RP51/PMD11/PMA11/RC3_33") (pintype "bidirectional"))
    )
    (net (code "66") (name "unconnected-(U1-AN16{slash}ISRC2{slash}RP55{slash}PMD8{slash}PMA8{slash}RC7-Pad40)") (class "Default")
      (node (ref "U1") (pin "40") (pinfunction "AN16/ISRC2/RP55/PMD8/PMA8/RC7_40") (pintype "bidirectional"))
    )
    (net (code "67") (name "unconnected-(U1-AN17{slash}ANN1{slash}IBIAS1{slash}RP54{slash}PMD12{slash}PMA12{slash}RC6-Pad30)") (class "Default")
      (node (ref "U1") (pin "30") (pinfunction "AN17/ANN1/IBIAS1/RP54/PMD12/PMA12/RC6_30") (pintype "bidirectional"))
    )
    (net (code "68") (name "unconnected-(U1-AN18{slash}CMP3C{slash}ISRC3{slash}RP74{slash}PMD9{slash}PMA9{slash}RD10-Pad38)") (class "Default")
      (node (ref "U1") (pin "38") (pinfunction "AN18/CMP3C/ISRC3/RP74/PMD9/PMA9/RD10_38") (pintype "bidirectional"))
    )
    (net (code "69") (name "unconnected-(U1-AN19{slash}CMP2C{slash}RP75{slash}PMA0{slash}PMALL{slash}PSA0{slash}RD11-Pad36)") (class "Default")
      (node (ref "U1") (pin "36") (pinfunction "AN19/CMP2C/RP75/PMA0/PMALL/PSA0/RD11_36") (pintype "bidirectional"))
    )
    (net (code "70") (name "unconnected-(U1-ANN2{slash}RP77{slash}RD13-Pad14)") (class "Default")
      (node (ref "U1") (pin "14") (pinfunction "ANN2/RP77/RD13_14") (pintype "bidirectional"))
    )
    (net (code "71") (name "unconnected-(U1-AVDD-Pad25)") (class "Default")
      (node (ref "U1") (pin "25") (pinfunction "AVDD_25") (pintype "power_in"))
    )
    (net (code "72") (name "unconnected-(U1-OA1IN+{slash}AN9{slash}PMA6{slash}RA2-Pad20)") (class "Default")
      (node (ref "U1") (pin "20") (pinfunction "OA1IN+/AN9/PMA6/RA2_20") (pintype "bidirectional"))
    )
    (net (code "73") (name "unconnected-(U1-OA3IN+{slash}AN14{slash}CMP2B{slash}ISRC1{slash}RP50{slash}PMD13{slash}PMA13{slash}RC2-Pad29)") (class "Default")
      (node (ref "U1") (pin "29") (pinfunction "OA3IN+/AN14/CMP2B/ISRC1/RP50/PMD13/PMA13/RC2_29") (pintype "bidirectional"))
    )
    (net (code "74") (name "unconnected-(U1-OA3IN-{slash}AN13{slash}CMP1B{slash}ISRC0{slash}RP49{slash}PMA7{slash}RC1-Pad28)") (class "Default")
      (node (ref "U1") (pin "28") (pinfunction "OA3IN-/AN13/CMP1B/ISRC0/RP49/PMA7/RC1_28") (pintype "bidirectional"))
    )
    (net (code "75") (name "unconnected-(U1-OSCO{slash}CLKO{slash}AN6{slash}RP33{slash}PMA1{slash}PMALH{slash}PSA1{slash}RB1-Pad35)") (class "Default")
      (node (ref "U1") (pin "35") (pinfunction "OSCO/CLKO/AN6/RP33/PMA1/PMALH/PSA1/RB1_35") (pintype "bidirectional"))
    )
    (net (code "76") (name "unconnected-(U1-PGC2{slash}OA2IN+{slash}RP36{slash}RB4-Pad45)") (class "Default")
      (node (ref "U1") (pin "45") (pinfunction "PGC2/OA2IN+/RP36/RB4_45") (pintype "bidirectional"))
    )
    (net (code "77") (name "unconnected-(U1-PGC3{slash}RP38{slash}SCL2{slash}RB6-Pad56)") (class "Default")
      (node (ref "U1") (pin "56") (pinfunction "PGC3/RP38/SCL2/RB6_56") (pintype "bidirectional"))
    )
    (net (code "78") (name "unconnected-(U1-PGD2{slash}OA2IN-{slash}AN8{slash}RP35{slash}RB3-Pad43)") (class "Default")
      (node (ref "U1") (pin "43") (pinfunction "PGD2/OA2IN-/AN8/RP35/RB3_43") (pintype "bidirectional"))
    )
    (net (code "79") (name "unconnected-(U1-PGD3{slash}RP37{slash}SDA2{slash}PMA14{slash}PMCS1{slash}PSCS{slash}RB5-Pad55)") (class "Default")
      (node (ref "U1") (pin "55") (pinfunction "PGD3/RP37/SDA2/PMA14/PMCS1/PSCS/RB5_55") (pintype "bidirectional"))
    )
    (net (code "80") (name "unconnected-(U1-RP52{slash}PWM5H{slash}ASDA2{slash}RC4-Pad63)") (class "Default")
      (node (ref "U1") (pin "63") (pinfunction "RP52/PWM5H/ASDA2/RC4_63") (pintype "bidirectional"))
    )
    (net (code "81") (name "unconnected-(U1-RP53{slash}PWM5L{slash}ASCL2{slash}PMWR{slash}PMENB{slash}PSWR{slash}RC5-Pad65)") (class "Default")
      (node (ref "U1") (pin "65") (pinfunction "RP53/PWM5L/ASCL2/PMWR/PMENB/PSWR/RC5_65") (pintype "bidirectional"))
    )
    (net (code "82") (name "unconnected-(U1-RP56{slash}ASDA1{slash}SCK2{slash}RC8-Pad46)") (class "Default")
      (node (ref "U1") (pin "46") (pinfunction "RP56/ASDA1/SCK2/RC8_46") (pintype "bidirectional"))
    )
    (net (code "83") (name "unconnected-(U1-RP57{slash}ASCL1{slash}SDI2{slash}RC9-Pad47)") (class "Default")
      (node (ref "U1") (pin "47") (pinfunction "RP57/ASCL1/SDI2/RC9_47") (pintype "bidirectional"))
    )
    (net (code "84") (name "unconnected-(U1-RP58{slash}PWM7H{slash}PMRD{slash}*PMWR{slash}PSRD{slash}RC10-Pad66)") (class "Default")
      (node (ref "U1") (pin "66") (pinfunction "RP58/PWM7H/PMRD/*PMWR/PSRD/RC10_66") (pintype "bidirectional"))
    )
    (net (code "85") (name "unconnected-(U1-RP59{slash}PWM7L{slash}RC11-Pad67)") (class "Default")
      (node (ref "U1") (pin "67") (pinfunction "RP59/PWM7L/RC11_67") (pintype "bidirectional"))
    )
    (net (code "86") (name "unconnected-(U1-RP60{slash}PWM8H{slash}PMD7{slash}RC12-Pad5)") (class "Default")
      (node (ref "U1") (pin "5") (pinfunction "RP60/PWM8H/PMD7/RC12_5") (pintype "bidirectional"))
    )
    (net (code "87") (name "unconnected-(U1-RP61{slash}PWM8L{slash}PMA5{slash}RC13-Pad6)") (class "Default")
      (node (ref "U1") (pin "6") (pinfunction "RP61/PWM8L/PMA5/RC13_6") (pintype "bidirectional"))
    )
    (net (code "88") (name "unconnected-(U1-RP62{slash}PWM6H{slash}PMA4{slash}RC14-Pad7)") (class "Default")
      (node (ref "U1") (pin "7") (pinfunction "RP62/PWM6H/PMA4/RC14_7") (pintype "bidirectional"))
    )
    (net (code "89") (name "unconnected-(U1-RP63{slash}PWM6L{slash}PMA3{slash}RC15-Pad8)") (class "Default")
      (node (ref "U1") (pin "8") (pinfunction "RP63/PWM6L/PMA3/RC15_8") (pintype "bidirectional"))
    )
    (net (code "90") (name "unconnected-(U1-RP64{slash}PWM4L{slash}PMD0{slash}RD0-Pad74)") (class "Default")
      (node (ref "U1") (pin "74") (pinfunction "RP64/PWM4L/PMD0/RD0_74") (pintype "bidirectional"))
    )
    (net (code "91") (name "unconnected-(U1-RP65{slash}PWM4H{slash}RD1-Pad73)") (class "Default")
      (node (ref "U1") (pin "73") (pinfunction "RP65/PWM4H/RD1_73") (pintype "bidirectional"))
    )
    (net (code "92") (name "unconnected-(U1-RP66{slash}RD2-Pad72)") (class "Default")
      (node (ref "U1") (pin "72") (pinfunction "RP66/RD2_72") (pintype "bidirectional"))
    )
    (net (code "93") (name "unconnected-(U1-RP69{slash}PMA15{slash}PMCS2{slash}RD5-Pad54)") (class "Default")
      (node (ref "U1") (pin "54") (pinfunction "RP69/PMA15/PMCS2/RD5_54") (pintype "bidirectional"))
    )
    (net (code "94") (name "unconnected-(U1-RP70{slash}PMD14{slash}RD6-Pad53)") (class "Default")
      (node (ref "U1") (pin "53") (pinfunction "RP70/PMD14/RD6_53") (pintype "bidirectional"))
    )
    (net (code "95") (name "unconnected-(U1-RP71{slash}PMD15{slash}RD7-Pad52)") (class "Default")
      (node (ref "U1") (pin "52") (pinfunction "RP71/PMD15/RD7_52") (pintype "bidirectional"))
    )
    (net (code "96") (name "unconnected-(U1-RP72{slash}SDO2{slash}PCI19{slash}RD8-Pad49)") (class "Default")
      (node (ref "U1") (pin "49") (pinfunction "RP72/SDO2/PCI19/RD8_49") (pintype "bidirectional"))
    )
    (net (code "97") (name "unconnected-(U1-RP73{slash}PCI20{slash}RD9-Pad48)") (class "Default")
      (node (ref "U1") (pin "48") (pinfunction "RP73/PCI20/RD9_48") (pintype "bidirectional"))
    )
    (net (code "98") (name "unconnected-(U1-RP76{slash}RD12-Pad27)") (class "Default")
      (node (ref "U1") (pin "27") (pinfunction "RP76/RD12_27") (pintype "bidirectional"))
    )
    (net (code "99") (name "unconnected-(U1-RP78{slash}PCI21{slash}RD14-Pad13)") (class "Default")
      (node (ref "U1") (pin "13") (pinfunction "RP78/PCI21/RD14_13") (pintype "bidirectional"))
    )
    (net (code "100") (name "unconnected-(U1-RP79{slash}PCI22{slash}PMA2{slash}RD15-Pad10)") (class "Default")
      (node (ref "U1") (pin "10") (pinfunction "RP79/PCI22/PMA2/RD15_10") (pintype "bidirectional"))
    )
    (net (code "101") (name "unconnected-(U1-TDO{slash}AN2{slash}CMP3A{slash}RP39{slash}SDA3{slash}RB7-Pad58)") (class "Default")
      (node (ref "U1") (pin "58") (pinfunction "TDO/AN2/CMP3A/RP39/SDA3/RB7_58") (pintype "bidirectional"))
    )
  )
)
